# double-tube.net
KiCad netlist of a schematic drawn in EAGLE
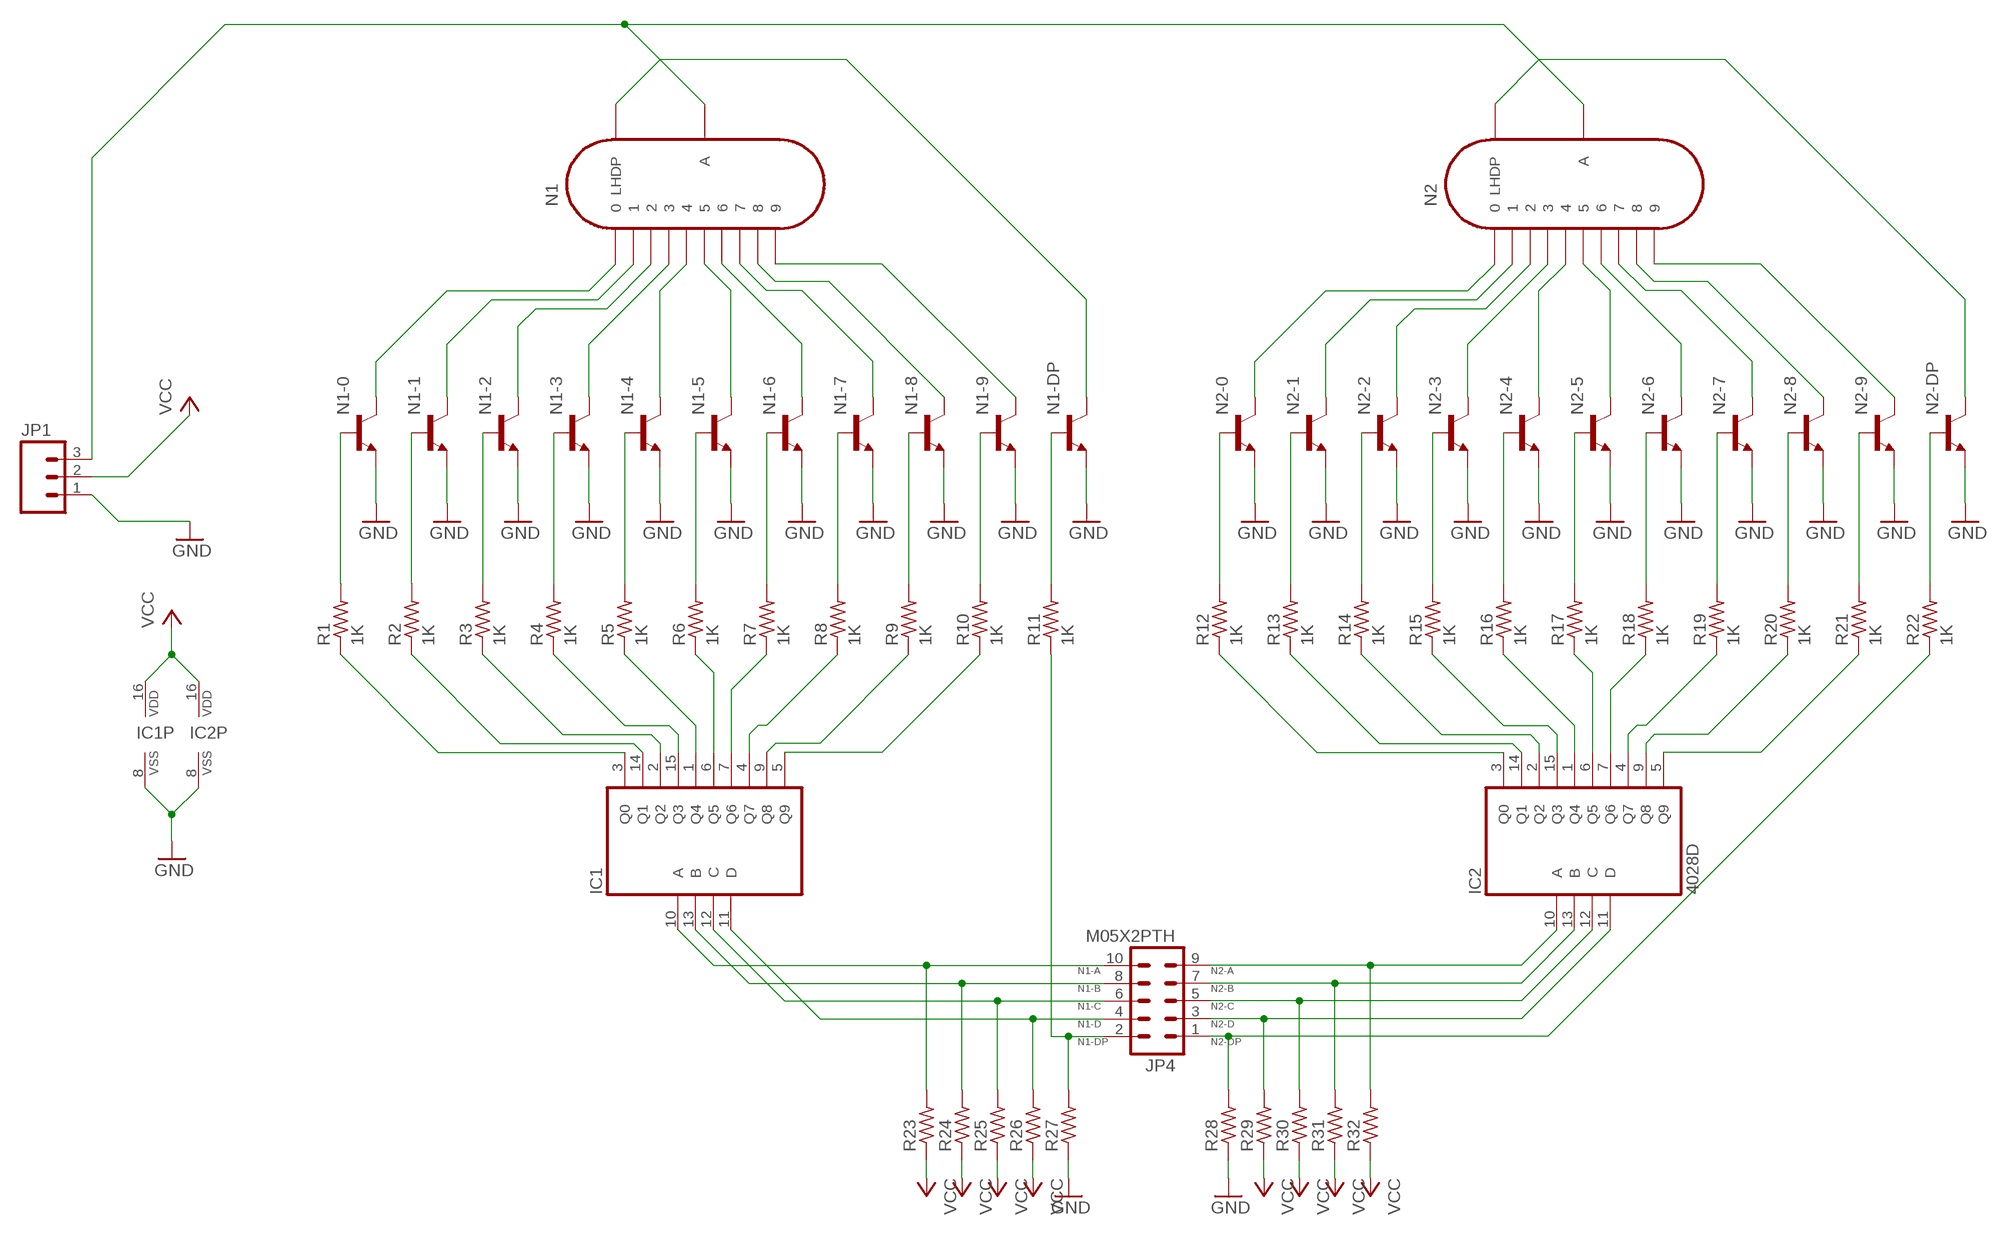
[diagram p0: schematic, sheet 1]

(export (version "E")
  (design (tool "Eeschema 10.0.6"))
  (components
    (comp (ref "IC1")
      (value "4028D")
      (footprint "eagle-import:SO16")
      (libsource (lib "eagle-import") (part "4028D"))
    )
    (comp (ref "IC2")
      (value "4028D")
      (footprint "eagle-import:SO16")
      (libsource (lib "eagle-import") (part "4028D"))
    )
    (comp (ref "JP1")
      (value "M03PTH")
      (footprint "eagle-import:1X03")
      (libsource (lib "eagle-import") (part "M03PTH"))
    )
    (comp (ref "JP4")
      (value "M05X2PTH")
      (footprint "eagle-import:AVR_ICSP")
      (libsource (lib "eagle-import") (part "M05X2PTH"))
    )
    (comp (ref "N1")
      (value "IN-12B")
      (footprint "eagle-import:IN-12")
      (libsource (lib "eagle-import") (part "IN-12B"))
    )
    (comp (ref "N1-0")
      (value "NPN_SMD")
      (footprint "eagle-import:SOT-23")
      (libsource (lib "eagle-import") (part "NPN_SMD"))
    )
    (comp (ref "N1-1")
      (value "NPN_SMD")
      (footprint "eagle-import:SOT-23")
      (libsource (lib "eagle-import") (part "NPN_SMD"))
    )
    (comp (ref "N1-2")
      (value "NPN_SMD")
      (footprint "eagle-import:SOT-23")
      (libsource (lib "eagle-import") (part "NPN_SMD"))
    )
    (comp (ref "N1-3")
      (value "NPN_SMD")
      (footprint "eagle-import:SOT-23")
      (libsource (lib "eagle-import") (part "NPN_SMD"))
    )
    (comp (ref "N1-4")
      (value "NPN_SMD")
      (footprint "eagle-import:SOT-23")
      (libsource (lib "eagle-import") (part "NPN_SMD"))
    )
    (comp (ref "N1-5")
      (value "NPN_SMD")
      (footprint "eagle-import:SOT-23")
      (libsource (lib "eagle-import") (part "NPN_SMD"))
    )
    (comp (ref "N1-6")
      (value "NPN_SMD")
      (footprint "eagle-import:SOT-23")
      (libsource (lib "eagle-import") (part "NPN_SMD"))
    )
    (comp (ref "N1-7")
      (value "NPN_SMD")
      (footprint "eagle-import:SOT-23")
      (libsource (lib "eagle-import") (part "NPN_SMD"))
    )
    (comp (ref "N1-8")
      (value "NPN_SMD")
      (footprint "eagle-import:SOT-23")
      (libsource (lib "eagle-import") (part "NPN_SMD"))
    )
    (comp (ref "N1-9")
      (value "NPN_SMD")
      (footprint "eagle-import:SOT-23")
      (libsource (lib "eagle-import") (part "NPN_SMD"))
    )
    (comp (ref "N1-DP")
      (value "NPN_SMD")
      (footprint "eagle-import:SOT-23")
      (libsource (lib "eagle-import") (part "NPN_SMD"))
    )
    (comp (ref "N2")
      (value "IN-12B")
      (footprint "eagle-import:IN-12")
      (libsource (lib "eagle-import") (part "IN-12B"))
    )
    (comp (ref "N2-0")
      (value "NPN_SMD")
      (footprint "eagle-import:SOT-23")
      (libsource (lib "eagle-import") (part "NPN_SMD"))
    )
    (comp (ref "N2-1")
      (value "NPN_SMD")
      (footprint "eagle-import:SOT-23")
      (libsource (lib "eagle-import") (part "NPN_SMD"))
    )
    (comp (ref "N2-2")
      (value "NPN_SMD")
      (footprint "eagle-import:SOT-23")
      (libsource (lib "eagle-import") (part "NPN_SMD"))
    )
    (comp (ref "N2-3")
      (value "NPN_SMD")
      (footprint "eagle-import:SOT-23")
      (libsource (lib "eagle-import") (part "NPN_SMD"))
    )
    (comp (ref "N2-4")
      (value "NPN_SMD")
      (footprint "eagle-import:SOT-23")
      (libsource (lib "eagle-import") (part "NPN_SMD"))
    )
    (comp (ref "N2-5")
      (value "NPN_SMD")
      (footprint "eagle-import:SOT-23")
      (libsource (lib "eagle-import") (part "NPN_SMD"))
    )
    (comp (ref "N2-6")
      (value "NPN_SMD")
      (footprint "eagle-import:SOT-23")
      (libsource (lib "eagle-import") (part "NPN_SMD"))
    )
    (comp (ref "N2-7")
      (value "NPN_SMD")
      (footprint "eagle-import:SOT-23")
      (libsource (lib "eagle-import") (part "NPN_SMD"))
    )
    (comp (ref "N2-8")
      (value "NPN_SMD")
      (footprint "eagle-import:SOT-23")
      (libsource (lib "eagle-import") (part "NPN_SMD"))
    )
    (comp (ref "N2-9")
      (value "NPN_SMD")
      (footprint "eagle-import:SOT-23")
      (libsource (lib "eagle-import") (part "NPN_SMD"))
    )
    (comp (ref "N2-DP")
      (value "NPN_SMD")
      (footprint "eagle-import:SOT-23")
      (libsource (lib "eagle-import") (part "NPN_SMD"))
    )
    (comp (ref "R1")
      (value "1K")
      (footprint "eagle-import:R0603")
      (libsource (lib "eagle-import") (part "RESISTORR0603"))
    )
    (comp (ref "R2")
      (value "1K")
      (footprint "eagle-import:R0603")
      (libsource (lib "eagle-import") (part "RESISTORR0603"))
    )
    (comp (ref "R3")
      (value "1K")
      (footprint "eagle-import:R0603")
      (libsource (lib "eagle-import") (part "RESISTORR0603"))
    )
    (comp (ref "R4")
      (value "1K")
      (footprint "eagle-import:R0603")
      (libsource (lib "eagle-import") (part "RESISTORR0603"))
    )
    (comp (ref "R5")
      (value "1K")
      (footprint "eagle-import:R0603")
      (libsource (lib "eagle-import") (part "RESISTORR0603"))
    )
    (comp (ref "R6")
      (value "1K")
      (footprint "eagle-import:R0603")
      (libsource (lib "eagle-import") (part "RESISTORR0603"))
    )
    (comp (ref "R7")
      (value "1K")
      (footprint "eagle-import:R0603")
      (libsource (lib "eagle-import") (part "RESISTORR0603"))
    )
    (comp (ref "R8")
      (value "1K")
      (footprint "eagle-import:R0603")
      (libsource (lib "eagle-import") (part "RESISTORR0603"))
    )
    (comp (ref "R9")
      (value "1K")
      (footprint "eagle-import:R0603")
      (libsource (lib "eagle-import") (part "RESISTORR0603"))
    )
    (comp (ref "R10")
      (value "1K")
      (footprint "eagle-import:R0603")
      (libsource (lib "eagle-import") (part "RESISTORR0603"))
    )
    (comp (ref "R11")
      (value "1K")
      (footprint "eagle-import:R0603")
      (libsource (lib "eagle-import") (part "RESISTORR0603"))
    )
    (comp (ref "R12")
      (value "1K")
      (footprint "eagle-import:R0603")
      (libsource (lib "eagle-import") (part "RESISTORR0603"))
    )
    (comp (ref "R13")
      (value "1K")
      (footprint "eagle-import:R0603")
      (libsource (lib "eagle-import") (part "RESISTORR0603"))
    )
    (comp (ref "R14")
      (value "1K")
      (footprint "eagle-import:R0603")
      (libsource (lib "eagle-import") (part "RESISTORR0603"))
    )
    (comp (ref "R15")
      (value "1K")
      (footprint "eagle-import:R0603")
      (libsource (lib "eagle-import") (part "RESISTORR0603"))
    )
    (comp (ref "R16")
      (value "1K")
      (footprint "eagle-import:R0603")
      (libsource (lib "eagle-import") (part "RESISTORR0603"))
    )
    (comp (ref "R17")
      (value "1K")
      (footprint "eagle-import:R0603")
      (libsource (lib "eagle-import") (part "RESISTORR0603"))
    )
    (comp (ref "R18")
      (value "1K")
      (footprint "eagle-import:R0603")
      (libsource (lib "eagle-import") (part "RESISTORR0603"))
    )
    (comp (ref "R19")
      (value "1K")
      (footprint "eagle-import:R0603")
      (libsource (lib "eagle-import") (part "RESISTORR0603"))
    )
    (comp (ref "R20")
      (value "1K")
      (footprint "eagle-import:R0603")
      (libsource (lib "eagle-import") (part "RESISTORR0603"))
    )
    (comp (ref "R21")
      (value "1K")
      (footprint "eagle-import:R0603")
      (libsource (lib "eagle-import") (part "RESISTORR0603"))
    )
    (comp (ref "R22")
      (value "1K")
      (footprint "eagle-import:R0603")
      (libsource (lib "eagle-import") (part "RESISTORR0603"))
    )
    (comp (ref "R23")
      (value "RESISTORR0603")
      (footprint "eagle-import:R0603")
      (libsource (lib "eagle-import") (part "RESISTORR0603"))
    )
    (comp (ref "R24")
      (value "RESISTORR0603")
      (footprint "eagle-import:R0603")
      (libsource (lib "eagle-import") (part "RESISTORR0603"))
    )
    (comp (ref "R25")
      (value "RESISTORR0603")
      (footprint "eagle-import:R0603")
      (libsource (lib "eagle-import") (part "RESISTORR0603"))
    )
    (comp (ref "R26")
      (value "RESISTORR0603")
      (footprint "eagle-import:R0603")
      (libsource (lib "eagle-import") (part "RESISTORR0603"))
    )
    (comp (ref "R27")
      (value "RESISTORR0603")
      (footprint "eagle-import:R0603")
      (libsource (lib "eagle-import") (part "RESISTORR0603"))
    )
    (comp (ref "R28")
      (value "RESISTORR0603")
      (footprint "eagle-import:R0603")
      (libsource (lib "eagle-import") (part "RESISTORR0603"))
    )
    (comp (ref "R29")
      (value "RESISTORR0603")
      (footprint "eagle-import:R0603")
      (libsource (lib "eagle-import") (part "RESISTORR0603"))
    )
    (comp (ref "R30")
      (value "RESISTORR0603")
      (footprint "eagle-import:R0603")
      (libsource (lib "eagle-import") (part "RESISTORR0603"))
    )
    (comp (ref "R31")
      (value "RESISTORR0603")
      (footprint "eagle-import:R0603")
      (libsource (lib "eagle-import") (part "RESISTORR0603"))
    )
    (comp (ref "R32")
      (value "RESISTORR0603")
      (footprint "eagle-import:R0603")
      (libsource (lib "eagle-import") (part "RESISTORR0603"))
    )
  )
  (nets
    (net (code "1") (name "/N1-A") (class "Default")
      (node (ref "IC1") (pin "10") (pinfunction "A_10") (pintype "input"))
      (node (ref "JP4") (pin "10") (pinfunction "10_10") (pintype "passive"))
      (node (ref "R23") (pin "2") (pinfunction "2_2") (pintype "passive"))
    )
    (net (code "2") (name "/N1-B") (class "Default")
      (node (ref "IC1") (pin "13") (pinfunction "B_13") (pintype "input"))
      (node (ref "JP4") (pin "8") (pinfunction "8_8") (pintype "passive"))
      (node (ref "R24") (pin "2") (pinfunction "2_2") (pintype "passive"))
    )
    (net (code "3") (name "/N1-C") (class "Default")
      (node (ref "IC1") (pin "12") (pinfunction "C_12") (pintype "input"))
      (node (ref "JP4") (pin "6") (pinfunction "6_6") (pintype "passive"))
      (node (ref "R25") (pin "2") (pinfunction "2_2") (pintype "passive"))
    )
    (net (code "4") (name "/N1-D") (class "Default")
      (node (ref "IC1") (pin "11") (pinfunction "D_11") (pintype "input"))
      (node (ref "JP4") (pin "4") (pinfunction "4_4") (pintype "passive"))
      (node (ref "R26") (pin "2") (pinfunction "2_2") (pintype "passive"))
    )
    (net (code "5") (name "/N1-DP") (class "Default")
      (node (ref "JP4") (pin "2") (pinfunction "2_2") (pintype "passive"))
      (node (ref "R11") (pin "1") (pinfunction "1_1") (pintype "passive"))
      (node (ref "R27") (pin "2") (pinfunction "2_2") (pintype "passive"))
    )
    (net (code "6") (name "/N2-A") (class "Default")
      (node (ref "IC2") (pin "10") (pinfunction "A_10") (pintype "input"))
      (node (ref "JP4") (pin "9") (pinfunction "9_9") (pintype "passive"))
      (node (ref "R32") (pin "2") (pinfunction "2_2") (pintype "passive"))
    )
    (net (code "7") (name "/N2-B") (class "Default")
      (node (ref "IC2") (pin "13") (pinfunction "B_13") (pintype "input"))
      (node (ref "JP4") (pin "7") (pinfunction "7_7") (pintype "passive"))
      (node (ref "R31") (pin "2") (pinfunction "2_2") (pintype "passive"))
    )
    (net (code "8") (name "/N2-C") (class "Default")
      (node (ref "IC2") (pin "12") (pinfunction "C_12") (pintype "input"))
      (node (ref "JP4") (pin "5") (pinfunction "5_5") (pintype "passive"))
      (node (ref "R30") (pin "2") (pinfunction "2_2") (pintype "passive"))
    )
    (net (code "9") (name "/N2-D") (class "Default")
      (node (ref "IC2") (pin "11") (pinfunction "D_11") (pintype "input"))
      (node (ref "JP4") (pin "3") (pinfunction "3_3") (pintype "passive"))
      (node (ref "R29") (pin "2") (pinfunction "2_2") (pintype "passive"))
    )
    (net (code "10") (name "/N2-DP") (class "Default")
      (node (ref "JP4") (pin "1") (pinfunction "1_1") (pintype "passive"))
      (node (ref "R22") (pin "1") (pinfunction "1_1") (pintype "passive"))
      (node (ref "R28") (pin "2") (pinfunction "2_2") (pintype "passive"))
    )
    (net (code "11") (name "GND") (class "Default")
      (node (ref "IC1") (pin "8") (pinfunction "VSS_8") (pintype "power_in"))
      (node (ref "IC2") (pin "8") (pinfunction "VSS_8") (pintype "power_in"))
      (node (ref "JP1") (pin "1") (pinfunction "1_1") (pintype "passive"))
      (node (ref "N1-0") (pin "2") (pinfunction "E_2") (pintype "passive"))
      (node (ref "N1-1") (pin "2") (pinfunction "E_2") (pintype "passive"))
      (node (ref "N1-2") (pin "2") (pinfunction "E_2") (pintype "passive"))
      (node (ref "N1-3") (pin "2") (pinfunction "E_2") (pintype "passive"))
      (node (ref "N1-4") (pin "2") (pinfunction "E_2") (pintype "passive"))
      (node (ref "N1-5") (pin "2") (pinfunction "E_2") (pintype "passive"))
      (node (ref "N1-6") (pin "2") (pinfunction "E_2") (pintype "passive"))
      (node (ref "N1-7") (pin "2") (pinfunction "E_2") (pintype "passive"))
      (node (ref "N1-8") (pin "2") (pinfunction "E_2") (pintype "passive"))
      (node (ref "N1-9") (pin "2") (pinfunction "E_2") (pintype "passive"))
      (node (ref "N1-DP") (pin "2") (pinfunction "E_2") (pintype "passive"))
      (node (ref "N2-0") (pin "2") (pinfunction "E_2") (pintype "passive"))
      (node (ref "N2-1") (pin "2") (pinfunction "E_2") (pintype "passive"))
      (node (ref "N2-2") (pin "2") (pinfunction "E_2") (pintype "passive"))
      (node (ref "N2-3") (pin "2") (pinfunction "E_2") (pintype "passive"))
      (node (ref "N2-4") (pin "2") (pinfunction "E_2") (pintype "passive"))
      (node (ref "N2-5") (pin "2") (pinfunction "E_2") (pintype "passive"))
      (node (ref "N2-6") (pin "2") (pinfunction "E_2") (pintype "passive"))
      (node (ref "N2-7") (pin "2") (pinfunction "E_2") (pintype "passive"))
      (node (ref "N2-8") (pin "2") (pinfunction "E_2") (pintype "passive"))
      (node (ref "N2-9") (pin "2") (pinfunction "E_2") (pintype "passive"))
      (node (ref "N2-DP") (pin "2") (pinfunction "E_2") (pintype "passive"))
      (node (ref "R27") (pin "1") (pinfunction "1_1") (pintype "passive"))
      (node (ref "R28") (pin "1") (pinfunction "1_1") (pintype "passive"))
    )
    (net (code "12") (name "Net-(IC1A-Q0)") (class "Default")
      (node (ref "IC1") (pin "3") (pinfunction "Q0_3") (pintype "output"))
      (node (ref "R1") (pin "1") (pinfunction "1_1") (pintype "passive"))
    )
    (net (code "13") (name "Net-(IC1A-Q1)") (class "Default")
      (node (ref "IC1") (pin "14") (pinfunction "Q1_14") (pintype "output"))
      (node (ref "R2") (pin "1") (pinfunction "1_1") (pintype "passive"))
    )
    (net (code "14") (name "Net-(IC1A-Q2)") (class "Default")
      (node (ref "IC1") (pin "2") (pinfunction "Q2_2") (pintype "output"))
      (node (ref "R3") (pin "1") (pinfunction "1_1") (pintype "passive"))
    )
    (net (code "15") (name "Net-(IC1A-Q3)") (class "Default")
      (node (ref "IC1") (pin "15") (pinfunction "Q3_15") (pintype "output"))
      (node (ref "R4") (pin "1") (pinfunction "1_1") (pintype "passive"))
    )
    (net (code "16") (name "Net-(IC1A-Q4)") (class "Default")
      (node (ref "IC1") (pin "1") (pinfunction "Q4_1") (pintype "output"))
      (node (ref "R5") (pin "1") (pinfunction "1_1") (pintype "passive"))
    )
    (net (code "17") (name "Net-(IC1A-Q5)") (class "Default")
      (node (ref "IC1") (pin "6") (pinfunction "Q5_6") (pintype "output"))
      (node (ref "R6") (pin "1") (pinfunction "1_1") (pintype "passive"))
    )
    (net (code "18") (name "Net-(IC1A-Q6)") (class "Default")
      (node (ref "IC1") (pin "7") (pinfunction "Q6_7") (pintype "output"))
      (node (ref "R7") (pin "1") (pinfunction "1_1") (pintype "passive"))
    )
    (net (code "19") (name "Net-(IC1A-Q7)") (class "Default")
      (node (ref "IC1") (pin "4") (pinfunction "Q7_4") (pintype "output"))
      (node (ref "R8") (pin "1") (pinfunction "1_1") (pintype "passive"))
    )
    (net (code "20") (name "Net-(IC1A-Q8)") (class "Default")
      (node (ref "IC1") (pin "9") (pinfunction "Q8_9") (pintype "output"))
      (node (ref "R9") (pin "1") (pinfunction "1_1") (pintype "passive"))
    )
    (net (code "21") (name "Net-(IC1A-Q9)") (class "Default")
      (node (ref "IC1") (pin "5") (pinfunction "Q9_5") (pintype "output"))
      (node (ref "R10") (pin "1") (pinfunction "1_1") (pintype "passive"))
    )
    (net (code "22") (name "Net-(IC2A-Q0)") (class "Default")
      (node (ref "IC2") (pin "3") (pinfunction "Q0_3") (pintype "output"))
      (node (ref "R12") (pin "1") (pinfunction "1_1") (pintype "passive"))
    )
    (net (code "23") (name "Net-(IC2A-Q1)") (class "Default")
      (node (ref "IC2") (pin "14") (pinfunction "Q1_14") (pintype "output"))
      (node (ref "R13") (pin "1") (pinfunction "1_1") (pintype "passive"))
    )
    (net (code "24") (name "Net-(IC2A-Q2)") (class "Default")
      (node (ref "IC2") (pin "2") (pinfunction "Q2_2") (pintype "output"))
      (node (ref "R14") (pin "1") (pinfunction "1_1") (pintype "passive"))
    )
    (net (code "25") (name "Net-(IC2A-Q3)") (class "Default")
      (node (ref "IC2") (pin "15") (pinfunction "Q3_15") (pintype "output"))
      (node (ref "R15") (pin "1") (pinfunction "1_1") (pintype "passive"))
    )
    (net (code "26") (name "Net-(IC2A-Q4)") (class "Default")
      (node (ref "IC2") (pin "1") (pinfunction "Q4_1") (pintype "output"))
      (node (ref "R16") (pin "1") (pinfunction "1_1") (pintype "passive"))
    )
    (net (code "27") (name "Net-(IC2A-Q5)") (class "Default")
      (node (ref "IC2") (pin "6") (pinfunction "Q5_6") (pintype "output"))
      (node (ref "R17") (pin "1") (pinfunction "1_1") (pintype "passive"))
    )
    (net (code "28") (name "Net-(IC2A-Q6)") (class "Default")
      (node (ref "IC2") (pin "7") (pinfunction "Q6_7") (pintype "output"))
      (node (ref "R18") (pin "1") (pinfunction "1_1") (pintype "passive"))
    )
    (net (code "29") (name "Net-(IC2A-Q7)") (class "Default")
      (node (ref "IC2") (pin "4") (pinfunction "Q7_4") (pintype "output"))
      (node (ref "R19") (pin "1") (pinfunction "1_1") (pintype "passive"))
    )
    (net (code "30") (name "Net-(IC2A-Q8)") (class "Default")
      (node (ref "IC2") (pin "9") (pinfunction "Q8_9") (pintype "output"))
      (node (ref "R20") (pin "1") (pinfunction "1_1") (pintype "passive"))
    )
    (net (code "31") (name "Net-(IC2A-Q9)") (class "Default")
      (node (ref "IC2") (pin "5") (pinfunction "Q9_5") (pintype "output"))
      (node (ref "R21") (pin "1") (pinfunction "1_1") (pintype "passive"))
    )
    (net (code "32") (name "Net-(JP1-Pad3)") (class "Default")
      (node (ref "JP1") (pin "3") (pinfunction "3_3") (pintype "passive"))
      (node (ref "N1") (pin "A") (pinfunction "A_A") (pintype "bidirectional"))
      (node (ref "N2") (pin "A") (pinfunction "A_A") (pintype "bidirectional"))
    )
    (net (code "33") (name "Net-(N1-0-B)") (class "Default")
      (node (ref "N1-0") (pin "1") (pinfunction "B_1") (pintype "passive"))
      (node (ref "R1") (pin "2") (pinfunction "2_2") (pintype "passive"))
    )
    (net (code "34") (name "Net-(N1-0-C)") (class "Default")
      (node (ref "N1") (pin "0") (pinfunction "0_0") (pintype "bidirectional"))
      (node (ref "N1-0") (pin "3") (pinfunction "C_3") (pintype "passive"))
    )
    (net (code "35") (name "Net-(N1-1-B)") (class "Default")
      (node (ref "N1-1") (pin "1") (pinfunction "B_1") (pintype "passive"))
      (node (ref "R2") (pin "2") (pinfunction "2_2") (pintype "passive"))
    )
    (net (code "36") (name "Net-(N1-1-C)") (class "Default")
      (node (ref "N1") (pin "1") (pinfunction "1_1") (pintype "bidirectional"))
      (node (ref "N1-1") (pin "3") (pinfunction "C_3") (pintype "passive"))
    )
    (net (code "37") (name "Net-(N1-2-B)") (class "Default")
      (node (ref "N1-2") (pin "1") (pinfunction "B_1") (pintype "passive"))
      (node (ref "R3") (pin "2") (pinfunction "2_2") (pintype "passive"))
    )
    (net (code "38") (name "Net-(N1-2-C)") (class "Default")
      (node (ref "N1") (pin "2") (pinfunction "2_2") (pintype "bidirectional"))
      (node (ref "N1-2") (pin "3") (pinfunction "C_3") (pintype "passive"))
    )
    (net (code "39") (name "Net-(N1-3-B)") (class "Default")
      (node (ref "N1-3") (pin "1") (pinfunction "B_1") (pintype "passive"))
      (node (ref "R4") (pin "2") (pinfunction "2_2") (pintype "passive"))
    )
    (net (code "40") (name "Net-(N1-3-C)") (class "Default")
      (node (ref "N1") (pin "3") (pinfunction "3_3") (pintype "bidirectional"))
      (node (ref "N1-3") (pin "3") (pinfunction "C_3") (pintype "passive"))
    )
    (net (code "41") (name "Net-(N1-4-B)") (class "Default")
      (node (ref "N1-4") (pin "1") (pinfunction "B_1") (pintype "passive"))
      (node (ref "R5") (pin "2") (pinfunction "2_2") (pintype "passive"))
    )
    (net (code "42") (name "Net-(N1-4-C)") (class "Default")
      (node (ref "N1") (pin "4") (pinfunction "4_4") (pintype "bidirectional"))
      (node (ref "N1-4") (pin "3") (pinfunction "C_3") (pintype "passive"))
    )
    (net (code "43") (name "Net-(N1-5-B)") (class "Default")
      (node (ref "N1-5") (pin "1") (pinfunction "B_1") (pintype "passive"))
      (node (ref "R6") (pin "2") (pinfunction "2_2") (pintype "passive"))
    )
    (net (code "44") (name "Net-(N1-5-C)") (class "Default")
      (node (ref "N1") (pin "5") (pinfunction "5_5") (pintype "bidirectional"))
      (node (ref "N1-5") (pin "3") (pinfunction "C_3") (pintype "passive"))
    )
    (net (code "45") (name "Net-(N1-6-B)") (class "Default")
      (node (ref "N1-6") (pin "1") (pinfunction "B_1") (pintype "passive"))
      (node (ref "R7") (pin "2") (pinfunction "2_2") (pintype "passive"))
    )
    (net (code "46") (name "Net-(N1-6-C)") (class "Default")
      (node (ref "N1") (pin "6") (pinfunction "6_6") (pintype "bidirectional"))
      (node (ref "N1-6") (pin "3") (pinfunction "C_3") (pintype "passive"))
    )
    (net (code "47") (name "Net-(N1-7-B)") (class "Default")
      (node (ref "N1-7") (pin "1") (pinfunction "B_1") (pintype "passive"))
      (node (ref "R8") (pin "2") (pinfunction "2_2") (pintype "passive"))
    )
    (net (code "48") (name "Net-(N1-7-C)") (class "Default")
      (node (ref "N1") (pin "7") (pinfunction "7_7") (pintype "bidirectional"))
      (node (ref "N1-7") (pin "3") (pinfunction "C_3") (pintype "passive"))
    )
    (net (code "49") (name "Net-(N1-8-B)") (class "Default")
      (node (ref "N1-8") (pin "1") (pinfunction "B_1") (pintype "passive"))
      (node (ref "R9") (pin "2") (pinfunction "2_2") (pintype "passive"))
    )
    (net (code "50") (name "Net-(N1-8-C)") (class "Default")
      (node (ref "N1") (pin "8") (pinfunction "8_8") (pintype "bidirectional"))
      (node (ref "N1-8") (pin "3") (pinfunction "C_3") (pintype "passive"))
    )
    (net (code "51") (name "Net-(N1-9-B)") (class "Default")
      (node (ref "N1-9") (pin "1") (pinfunction "B_1") (pintype "passive"))
      (node (ref "R10") (pin "2") (pinfunction "2_2") (pintype "passive"))
    )
    (net (code "52") (name "Net-(N1-9-C)") (class "Default")
      (node (ref "N1") (pin "9") (pinfunction "9_9") (pintype "bidirectional"))
      (node (ref "N1-9") (pin "3") (pinfunction "C_3") (pintype "passive"))
    )
    (net (code "53") (name "Net-(N1-DP-B)") (class "Default")
      (node (ref "N1-DP") (pin "1") (pinfunction "B_1") (pintype "passive"))
      (node (ref "R11") (pin "2") (pinfunction "2_2") (pintype "passive"))
    )
    (net (code "54") (name "Net-(N1-DP-C)") (class "Default")
      (node (ref "N1") (pin "LHDP") (pinfunction "LHDP_LHDP") (pintype "bidirectional"))
      (node (ref "N1-DP") (pin "3") (pinfunction "C_3") (pintype "passive"))
    )
    (net (code "55") (name "Net-(N2-0-B)") (class "Default")
      (node (ref "N2-0") (pin "1") (pinfunction "B_1") (pintype "passive"))
      (node (ref "R12") (pin "2") (pinfunction "2_2") (pintype "passive"))
    )
    (net (code "56") (name "Net-(N2-0-C)") (class "Default")
      (node (ref "N2") (pin "0") (pinfunction "0_0") (pintype "bidirectional"))
      (node (ref "N2-0") (pin "3") (pinfunction "C_3") (pintype "passive"))
    )
    (net (code "57") (name "Net-(N2-1-B)") (class "Default")
      (node (ref "N2-1") (pin "1") (pinfunction "B_1") (pintype "passive"))
      (node (ref "R13") (pin "2") (pinfunction "2_2") (pintype "passive"))
    )
    (net (code "58") (name "Net-(N2-1-C)") (class "Default")
      (node (ref "N2") (pin "1") (pinfunction "1_1") (pintype "bidirectional"))
      (node (ref "N2-1") (pin "3") (pinfunction "C_3") (pintype "passive"))
    )
    (net (code "59") (name "Net-(N2-2-B)") (class "Default")
      (node (ref "N2-2") (pin "1") (pinfunction "B_1") (pintype "passive"))
      (node (ref "R14") (pin "2") (pinfunction "2_2") (pintype "passive"))
    )
    (net (code "60") (name "Net-(N2-2-C)") (class "Default")
      (node (ref "N2") (pin "2") (pinfunction "2_2") (pintype "bidirectional"))
      (node (ref "N2-2") (pin "3") (pinfunction "C_3") (pintype "passive"))
    )
    (net (code "61") (name "Net-(N2-3-B)") (class "Default")
      (node (ref "N2-3") (pin "1") (pinfunction "B_1") (pintype "passive"))
      (node (ref "R15") (pin "2") (pinfunction "2_2") (pintype "passive"))
    )
    (net (code "62") (name "Net-(N2-3-C)") (class "Default")
      (node (ref "N2") (pin "3") (pinfunction "3_3") (pintype "bidirectional"))
      (node (ref "N2-3") (pin "3") (pinfunction "C_3") (pintype "passive"))
    )
    (net (code "63") (name "Net-(N2-4-B)") (class "Default")
      (node (ref "N2-4") (pin "1") (pinfunction "B_1") (pintype "passive"))
      (node (ref "R16") (pin "2") (pinfunction "2_2") (pintype "passive"))
    )
    (net (code "64") (name "Net-(N2-4-C)") (class "Default")
      (node (ref "N2") (pin "4") (pinfunction "4_4") (pintype "bidirectional"))
      (node (ref "N2-4") (pin "3") (pinfunction "C_3") (pintype "passive"))
    )
    (net (code "65") (name "Net-(N2-5-B)") (class "Default")
      (node (ref "N2-5") (pin "1") (pinfunction "B_1") (pintype "passive"))
      (node (ref "R17") (pin "2") (pinfunction "2_2") (pintype "passive"))
    )
    (net (code "66") (name "Net-(N2-5-C)") (class "Default")
      (node (ref "N2") (pin "5") (pinfunction "5_5") (pintype "bidirectional"))
      (node (ref "N2-5") (pin "3") (pinfunction "C_3") (pintype "passive"))
    )
    (net (code "67") (name "Net-(N2-6-B)") (class "Default")
      (node (ref "N2-6") (pin "1") (pinfunction "B_1") (pintype "passive"))
      (node (ref "R18") (pin "2") (pinfunction "2_2") (pintype "passive"))
    )
    (net (code "68") (name "Net-(N2-6-C)") (class "Default")
      (node (ref "N2") (pin "6") (pinfunction "6_6") (pintype "bidirectional"))
      (node (ref "N2-6") (pin "3") (pinfunction "C_3") (pintype "passive"))
    )
    (net (code "69") (name "Net-(N2-7-B)") (class "Default")
      (node (ref "N2-7") (pin "1") (pinfunction "B_1") (pintype "passive"))
      (node (ref "R19") (pin "2") (pinfunction "2_2") (pintype "passive"))
    )
    (net (code "70") (name "Net-(N2-7-C)") (class "Default")
      (node (ref "N2") (pin "7") (pinfunction "7_7") (pintype "bidirectional"))
      (node (ref "N2-7") (pin "3") (pinfunction "C_3") (pintype "passive"))
    )
    (net (code "71") (name "Net-(N2-8-B)") (class "Default")
      (node (ref "N2-8") (pin "1") (pinfunction "B_1") (pintype "passive"))
      (node (ref "R20") (pin "2") (pinfunction "2_2") (pintype "passive"))
    )
    (net (code "72") (name "Net-(N2-8-C)") (class "Default")
      (node (ref "N2") (pin "8") (pinfunction "8_8") (pintype "bidirectional"))
      (node (ref "N2-8") (pin "3") (pinfunction "C_3") (pintype "passive"))
    )
    (net (code "73") (name "Net-(N2-9-B)") (class "Default")
      (node (ref "N2-9") (pin "1") (pinfunction "B_1") (pintype "passive"))
      (node (ref "R21") (pin "2") (pinfunction "2_2") (pintype "passive"))
    )
    (net (code "74") (name "Net-(N2-9-C)") (class "Default")
      (node (ref "N2") (pin "9") (pinfunction "9_9") (pintype "bidirectional"))
      (node (ref "N2-9") (pin "3") (pinfunction "C_3") (pintype "passive"))
    )
    (net (code "75") (name "Net-(N2-DP-B)") (class "Default")
      (node (ref "N2-DP") (pin "1") (pinfunction "B_1") (pintype "passive"))
      (node (ref "R22") (pin "2") (pinfunction "2_2") (pintype "passive"))
    )
    (net (code "76") (name "Net-(N2-DP-C)") (class "Default")
      (node (ref "N2") (pin "LHDP") (pinfunction "LHDP_LHDP") (pintype "bidirectional"))
      (node (ref "N2-DP") (pin "3") (pinfunction "C_3") (pintype "passive"))
    )
    (net (code "77") (name "VCC") (class "Default")
      (node (ref "IC1") (pin "16") (pinfunction "VDD_16") (pintype "power_in"))
      (node (ref "IC2") (pin "16") (pinfunction "VDD_16") (pintype "power_in"))
      (node (ref "JP1") (pin "2") (pinfunction "2_2") (pintype "passive"))
      (node (ref "R23") (pin "1") (pinfunction "1_1") (pintype "passive"))
      (node (ref "R24") (pin "1") (pinfunction "1_1") (pintype "passive"))
      (node (ref "R25") (pin "1") (pinfunction "1_1") (pintype "passive"))
      (node (ref "R26") (pin "1") (pinfunction "1_1") (pintype "passive"))
      (node (ref "R29") (pin "1") (pinfunction "1_1") (pintype "passive"))
      (node (ref "R30") (pin "1") (pinfunction "1_1") (pintype "passive"))
      (node (ref "R31") (pin "1") (pinfunction "1_1") (pintype "passive"))
      (node (ref "R32") (pin "1") (pinfunction "1_1") (pintype "passive"))
    )
  )
)
